# RasPi-feather.net
KiCad netlist of a schematic drawn in EAGLE
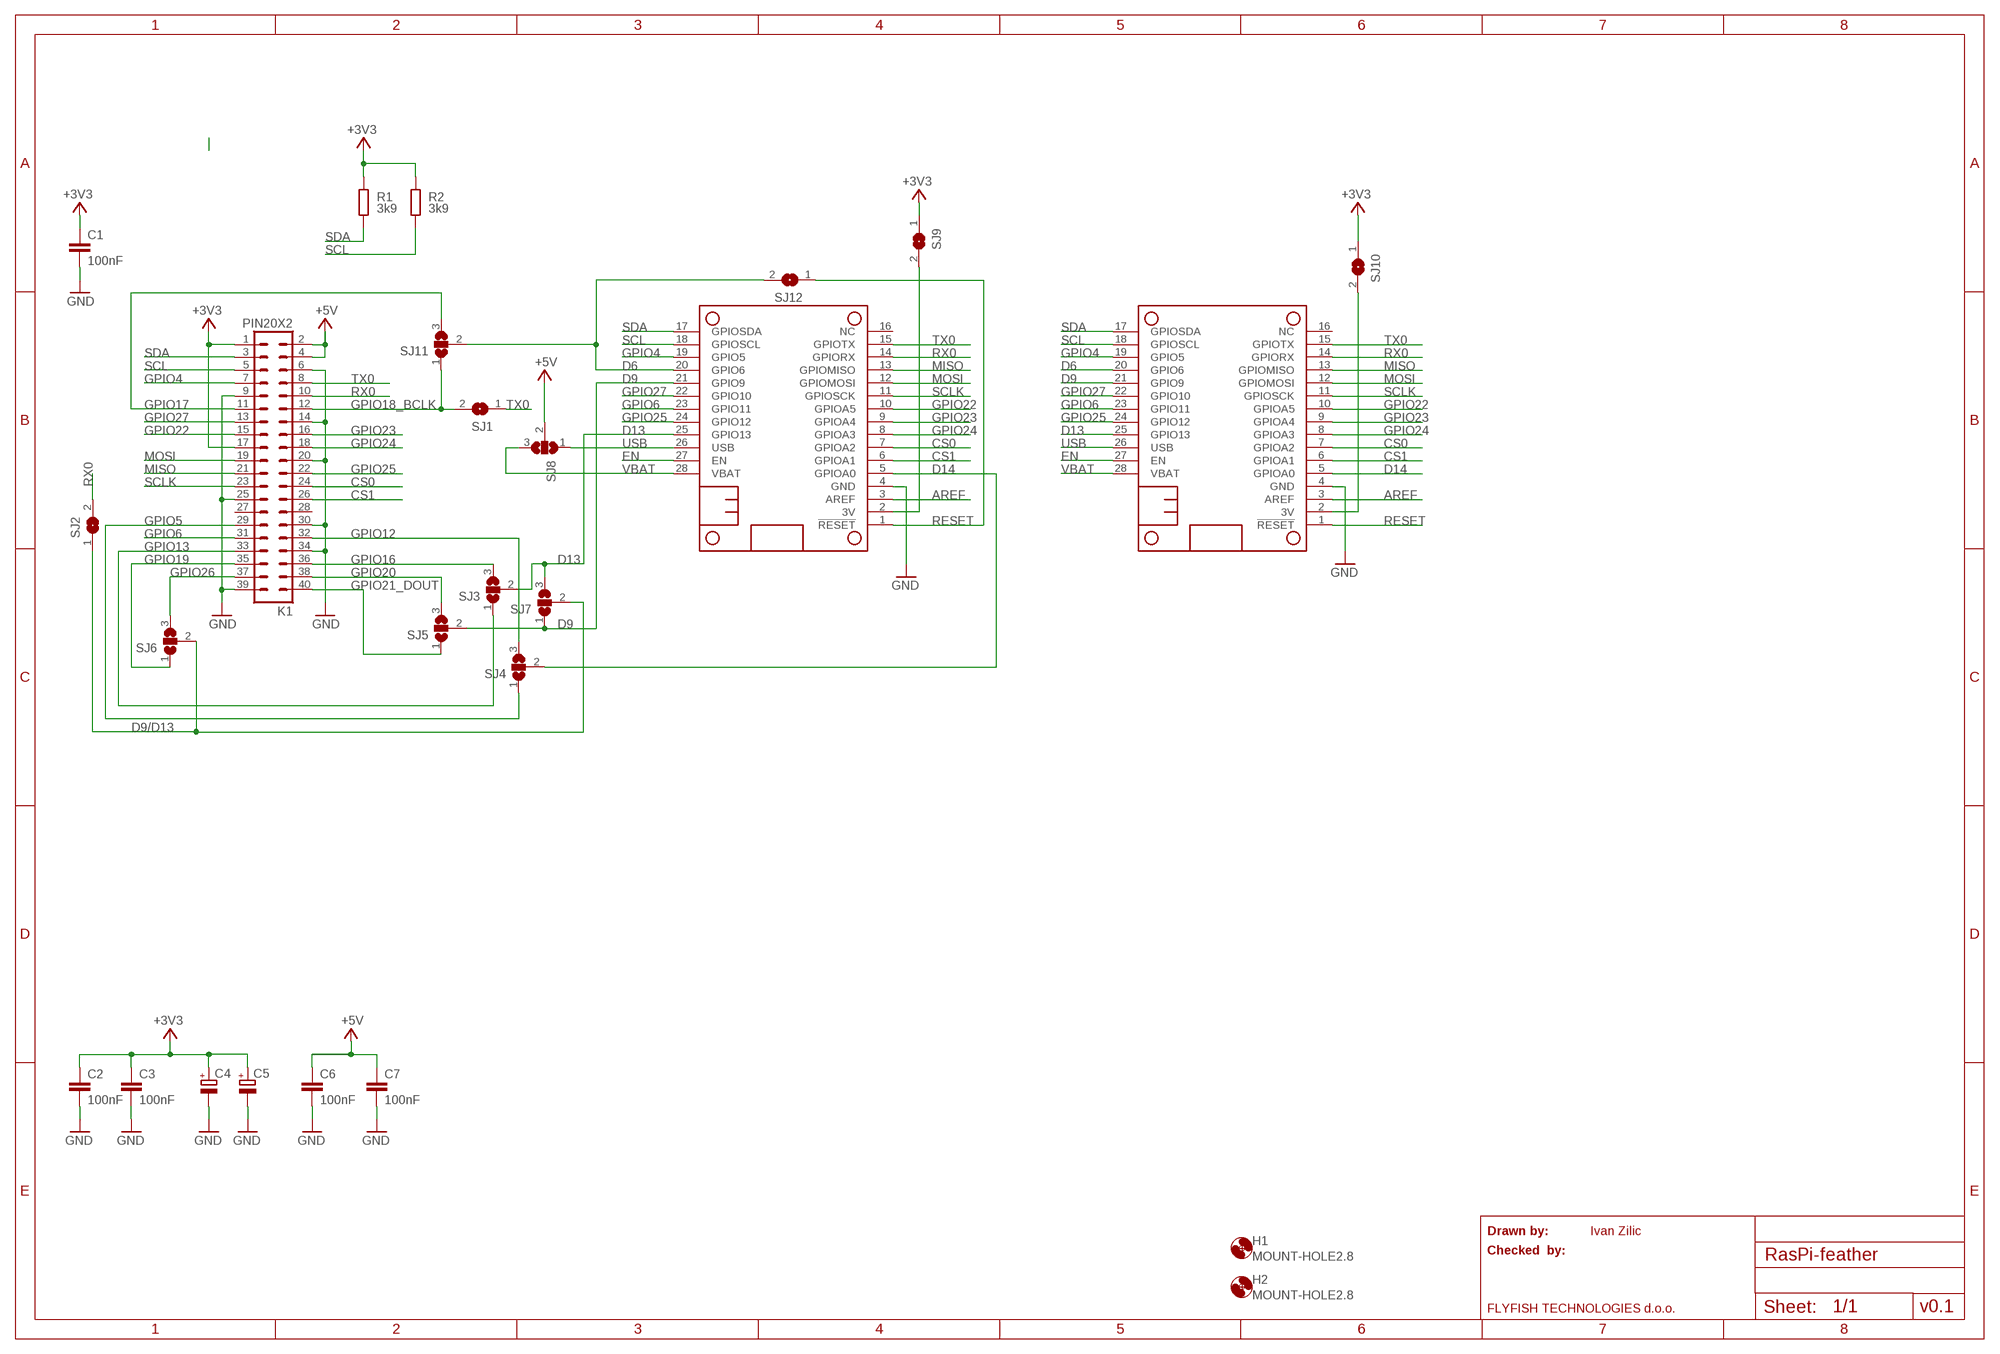
[diagram p0: schematic, sheet 1]

(export (version "E")
  (design (tool "Eeschema 10.0.6"))
  (components
    (comp (ref "C1")
      (value "100nF")
      (footprint "eagle-import:C0805K")
      (libsource (lib "eagle-import") (part "C-EUC0805K"))
    )
    (comp (ref "C2")
      (value "100nF")
      (footprint "eagle-import:C0805K")
      (libsource (lib "eagle-import") (part "C-EUC0805K"))
    )
    (comp (ref "C3")
      (value "100nF")
      (footprint "eagle-import:C0805K")
      (libsource (lib "eagle-import") (part "C-EUC0805K"))
    )
    (comp (ref "C4")
      (value "CPOL-EUSMCD")
      (footprint "eagle-import:SMC_D")
      (libsource (lib "eagle-import") (part "CPOL-EUSMCD"))
    )
    (comp (ref "C5")
      (value "CPOL-EUSMCD")
      (footprint "eagle-import:SMC_D")
      (libsource (lib "eagle-import") (part "CPOL-EUSMCD"))
    )
    (comp (ref "C6")
      (value "100nF")
      (footprint "eagle-import:C0805K")
      (libsource (lib "eagle-import") (part "C-EUC0805K"))
    )
    (comp (ref "C7")
      (value "100nF")
      (footprint "eagle-import:C0805K")
      (libsource (lib "eagle-import") (part "C-EUC0805K"))
    )
    (comp (ref "H1")
      (value "MOUNT-HOLE2.8")
      (footprint "eagle-import:2,8")
      (libsource (lib "eagle-import") (part "MOUNT-HOLE2.8"))
    )
    (comp (ref "H2")
      (value "MOUNT-HOLE2.8")
      (footprint "eagle-import:2,8")
      (libsource (lib "eagle-import") (part "MOUNT-HOLE2.8"))
    )
    (comp (ref "K1")
      (value "PIN20X2")
      (footprint "eagle-import:PIN_20X2")
      (libsource (lib "eagle-import") (part "PIN20X2"))
    )
    (comp (ref "MS1")
      (value "FEATHERWING_NODIM")
      (footprint "eagle-import:FEATHERWING_DIM")
      (libsource (lib "eagle-import") (part "FEATHERWING_NODIM"))
    )
    (comp (ref "MS2")
      (value "FEATHERWING_NODIM")
      (footprint "eagle-import:FEATHERWING_DIM")
      (libsource (lib "eagle-import") (part "FEATHERWING_NODIM"))
    )
    (comp (ref "R1")
      (value "3k9")
      (footprint "eagle-import:M0805")
      (fields (field (name "TOLERANCE") "5%"))
      (libsource (lib "eagle-import") (part "R-EU_M0805"))
    )
    (comp (ref "R2")
      (value "3k9")
      (footprint "eagle-import:M0805")
      (fields (field (name "TOLERANCE") "5%"))
      (libsource (lib "eagle-import") (part "R-EU_M0805"))
    )
    (comp (ref "SJ1") (value "SJ") (footprint "eagle-import:SJ") (libsource (lib "eagle-import") (part "SJ")))
    (comp (ref "SJ2") (value "SJ") (footprint "eagle-import:SJ") (libsource (lib "eagle-import") (part "SJ")))
    (comp (ref "SJ3")
      (value "SJ2W")
      (footprint "eagle-import:SJ_2")
      (libsource (lib "eagle-import") (part "SJ2W"))
    )
    (comp (ref "SJ4")
      (value "SJ2W")
      (footprint "eagle-import:SJ_2")
      (libsource (lib "eagle-import") (part "SJ2W"))
    )
    (comp (ref "SJ5")
      (value "SJ2W")
      (footprint "eagle-import:SJ_2")
      (libsource (lib "eagle-import") (part "SJ2W"))
    )
    (comp (ref "SJ6")
      (value "SJ2W")
      (footprint "eagle-import:SJ_2")
      (libsource (lib "eagle-import") (part "SJ2W"))
    )
    (comp (ref "SJ7")
      (value "SJ2W")
      (footprint "eagle-import:SJ_2")
      (libsource (lib "eagle-import") (part "SJ2W"))
    )
    (comp (ref "SJ8")
      (value "SJ2W")
      (footprint "eagle-import:SJ_2")
      (libsource (lib "eagle-import") (part "SJ2W"))
    )
    (comp (ref "SJ9") (value "SJ") (footprint "eagle-import:SJ") (libsource (lib "eagle-import") (part "SJ")))
    (comp (ref "SJ10")
      (value "SJ")
      (footprint "eagle-import:SJ")
      (libsource (lib "eagle-import") (part "SJ"))
    )
    (comp (ref "SJ11")
      (value "SJ2W")
      (footprint "eagle-import:SJ_2")
      (libsource (lib "eagle-import") (part "SJ2W"))
    )
    (comp (ref "SJ12")
      (value "SJ")
      (footprint "eagle-import:SJ")
      (libsource (lib "eagle-import") (part "SJ"))
    )
  )
  (nets
    (net (code "1") (name "+3V3") (class "Default")
      (node (ref "C1") (pin "1") (pinfunction "1_1") (pintype "passive"))
      (node (ref "C2") (pin "1") (pinfunction "1_1") (pintype "passive"))
      (node (ref "C3") (pin "1") (pinfunction "1_1") (pintype "passive"))
      (node (ref "C4") (pin "+") (pinfunction "+_+") (pintype "passive"))
      (node (ref "C5") (pin "+") (pinfunction "+_+") (pintype "passive"))
      (node (ref "K1") (pin "1") (pinfunction "1_1") (pintype "passive"))
      (node (ref "K1") (pin "17") (pinfunction "17_17") (pintype "passive"))
      (node (ref "R1") (pin "2") (pinfunction "2_2") (pintype "passive"))
      (node (ref "R2") (pin "2") (pinfunction "2_2") (pintype "passive"))
      (node (ref "SJ10") (pin "1") (pinfunction "1_1") (pintype "passive"))
      (node (ref "SJ9") (pin "1") (pinfunction "1_1") (pintype "passive"))
    )
    (net (code "2") (name "+5V") (class "Default")
      (node (ref "C6") (pin "1") (pinfunction "1_1") (pintype "passive"))
      (node (ref "C7") (pin "1") (pinfunction "1_1") (pintype "passive"))
      (node (ref "K1") (pin "2") (pinfunction "2_2") (pintype "passive"))
      (node (ref "K1") (pin "4") (pinfunction "4_4") (pintype "passive"))
      (node (ref "SJ8") (pin "2") (pinfunction "2_2") (pintype "passive"))
    )
    (net (code "3") (name "/AREF") (class "Default")
      (node (ref "MS1") (pin "3") (pinfunction "AREF_3") (pintype "passive"))
      (node (ref "MS2") (pin "3") (pinfunction "AREF_3") (pintype "passive"))
    )
    (net (code "4") (name "/CS0") (class "Default")
      (node (ref "K1") (pin "24") (pinfunction "24_24") (pintype "passive"))
      (node (ref "MS1") (pin "7") (pinfunction "GPIOA2_7") (pintype "bidirectional"))
      (node (ref "MS2") (pin "7") (pinfunction "GPIOA2_7") (pintype "bidirectional"))
    )
    (net (code "5") (name "/CS1") (class "Default")
      (node (ref "K1") (pin "26") (pinfunction "26_26") (pintype "passive"))
      (node (ref "MS1") (pin "6") (pinfunction "GPIOA1_6") (pintype "bidirectional"))
      (node (ref "MS2") (pin "6") (pinfunction "GPIOA1_6") (pintype "bidirectional"))
    )
    (net (code "6") (name "/D6") (class "Default")
      (node (ref "MS1") (pin "20") (pinfunction "GPIO6_20") (pintype "bidirectional"))
      (node (ref "MS2") (pin "20") (pinfunction "GPIO6_20") (pintype "bidirectional"))
      (node (ref "SJ11") (pin "2") (pinfunction "2_2") (pintype "passive"))
      (node (ref "SJ12") (pin "2") (pinfunction "2_2") (pintype "passive"))
    )
    (net (code "7") (name "/D9") (class "Default")
      (node (ref "MS1") (pin "21") (pinfunction "GPIO9_21") (pintype "bidirectional"))
      (node (ref "MS2") (pin "21") (pinfunction "GPIO9_21") (pintype "bidirectional"))
      (node (ref "SJ5") (pin "2") (pinfunction "2_2") (pintype "passive"))
      (node (ref "SJ7") (pin "1") (pinfunction "1_1") (pintype "passive"))
    )
    (net (code "8") (name "/D9{slash}D13") (class "Default")
      (node (ref "SJ2") (pin "1") (pinfunction "1_1") (pintype "passive"))
      (node (ref "SJ6") (pin "2") (pinfunction "2_2") (pintype "passive"))
      (node (ref "SJ7") (pin "2") (pinfunction "2_2") (pintype "passive"))
    )
    (net (code "9") (name "/D13") (class "Default")
      (node (ref "MS1") (pin "25") (pinfunction "GPIO13_25") (pintype "bidirectional"))
      (node (ref "MS2") (pin "25") (pinfunction "GPIO13_25") (pintype "bidirectional"))
      (node (ref "SJ3") (pin "2") (pinfunction "2_2") (pintype "passive"))
      (node (ref "SJ7") (pin "3") (pinfunction "3_3") (pintype "passive"))
    )
    (net (code "10") (name "/D14") (class "Default")
      (node (ref "MS1") (pin "5") (pinfunction "GPIOA0_5") (pintype "bidirectional"))
      (node (ref "MS2") (pin "5") (pinfunction "GPIOA0_5") (pintype "bidirectional"))
      (node (ref "SJ4") (pin "2") (pinfunction "2_2") (pintype "passive"))
    )
    (net (code "11") (name "/EN") (class "Default")
      (node (ref "MS1") (pin "27") (pinfunction "EN_27") (pintype "passive"))
      (node (ref "MS2") (pin "27") (pinfunction "EN_27") (pintype "passive"))
    )
    (net (code "12") (name "/GPIO4") (class "Default")
      (node (ref "K1") (pin "7") (pinfunction "7_7") (pintype "passive"))
      (node (ref "MS1") (pin "19") (pinfunction "GPIO5_19") (pintype "bidirectional"))
      (node (ref "MS2") (pin "19") (pinfunction "GPIO5_19") (pintype "bidirectional"))
    )
    (net (code "13") (name "/GPIO5") (class "Default")
      (node (ref "K1") (pin "29") (pinfunction "29_29") (pintype "passive"))
      (node (ref "SJ4") (pin "1") (pinfunction "1_1") (pintype "passive"))
    )
    (net (code "14") (name "/GPIO6") (class "Default")
      (node (ref "K1") (pin "31") (pinfunction "31_31") (pintype "passive"))
      (node (ref "MS1") (pin "23") (pinfunction "GPIO11_23") (pintype "bidirectional"))
      (node (ref "MS2") (pin "23") (pinfunction "GPIO11_23") (pintype "bidirectional"))
    )
    (net (code "15") (name "/GPIO12") (class "Default")
      (node (ref "K1") (pin "32") (pinfunction "32_32") (pintype "passive"))
      (node (ref "SJ4") (pin "3") (pinfunction "3_3") (pintype "passive"))
    )
    (net (code "16") (name "/GPIO13") (class "Default")
      (node (ref "K1") (pin "33") (pinfunction "33_33") (pintype "passive"))
      (node (ref "SJ3") (pin "1") (pinfunction "1_1") (pintype "passive"))
    )
    (net (code "17") (name "/GPIO16") (class "Default")
      (node (ref "K1") (pin "36") (pinfunction "36_36") (pintype "passive"))
      (node (ref "SJ3") (pin "3") (pinfunction "3_3") (pintype "passive"))
    )
    (net (code "18") (name "/GPIO17") (class "Default")
      (node (ref "K1") (pin "11") (pinfunction "11_11") (pintype "passive"))
      (node (ref "SJ11") (pin "3") (pinfunction "3_3") (pintype "passive"))
    )
    (net (code "19") (name "/GPIO18_BCLK") (class "Default")
      (node (ref "K1") (pin "12") (pinfunction "12_12") (pintype "passive"))
      (node (ref "SJ1") (pin "2") (pinfunction "2_2") (pintype "passive"))
      (node (ref "SJ11") (pin "1") (pinfunction "1_1") (pintype "passive"))
    )
    (net (code "20") (name "/GPIO19") (class "Default")
      (node (ref "K1") (pin "35") (pinfunction "35_35") (pintype "passive"))
      (node (ref "SJ6") (pin "1") (pinfunction "1_1") (pintype "passive"))
    )
    (net (code "21") (name "/GPIO20") (class "Default")
      (node (ref "K1") (pin "38") (pinfunction "38_38") (pintype "passive"))
      (node (ref "SJ5") (pin "3") (pinfunction "3_3") (pintype "passive"))
    )
    (net (code "22") (name "/GPIO21_DOUT") (class "Default")
      (node (ref "K1") (pin "40") (pinfunction "40_40") (pintype "passive"))
      (node (ref "SJ5") (pin "1") (pinfunction "1_1") (pintype "passive"))
    )
    (net (code "23") (name "/GPIO22") (class "Default")
      (node (ref "K1") (pin "15") (pinfunction "15_15") (pintype "passive"))
      (node (ref "MS1") (pin "10") (pinfunction "GPIOA5_10") (pintype "bidirectional"))
      (node (ref "MS2") (pin "10") (pinfunction "GPIOA5_10") (pintype "bidirectional"))
    )
    (net (code "24") (name "/GPIO23") (class "Default")
      (node (ref "K1") (pin "16") (pinfunction "16_16") (pintype "passive"))
      (node (ref "MS1") (pin "9") (pinfunction "GPIOA4_9") (pintype "bidirectional"))
      (node (ref "MS2") (pin "9") (pinfunction "GPIOA4_9") (pintype "bidirectional"))
    )
    (net (code "25") (name "/GPIO24") (class "Default")
      (node (ref "K1") (pin "18") (pinfunction "18_18") (pintype "passive"))
      (node (ref "MS1") (pin "8") (pinfunction "GPIOA3_8") (pintype "bidirectional"))
      (node (ref "MS2") (pin "8") (pinfunction "GPIOA3_8") (pintype "bidirectional"))
    )
    (net (code "26") (name "/GPIO25") (class "Default")
      (node (ref "K1") (pin "22") (pinfunction "22_22") (pintype "passive"))
      (node (ref "MS1") (pin "24") (pinfunction "GPIO12_24") (pintype "bidirectional"))
      (node (ref "MS2") (pin "24") (pinfunction "GPIO12_24") (pintype "bidirectional"))
    )
    (net (code "27") (name "/GPIO26") (class "Default")
      (node (ref "K1") (pin "37") (pinfunction "37_37") (pintype "passive"))
      (node (ref "SJ6") (pin "3") (pinfunction "3_3") (pintype "passive"))
    )
    (net (code "28") (name "/GPIO27") (class "Default")
      (node (ref "K1") (pin "13") (pinfunction "13_13") (pintype "passive"))
      (node (ref "MS1") (pin "22") (pinfunction "GPIO10_22") (pintype "bidirectional"))
      (node (ref "MS2") (pin "22") (pinfunction "GPIO10_22") (pintype "bidirectional"))
    )
    (net (code "29") (name "/MISO") (class "Default")
      (node (ref "K1") (pin "21") (pinfunction "21_21") (pintype "passive"))
      (node (ref "MS1") (pin "13") (pinfunction "GPIOMISO_13") (pintype "bidirectional"))
      (node (ref "MS2") (pin "13") (pinfunction "GPIOMISO_13") (pintype "bidirectional"))
    )
    (net (code "30") (name "/MOSI") (class "Default")
      (node (ref "K1") (pin "19") (pinfunction "19_19") (pintype "passive"))
      (node (ref "MS1") (pin "12") (pinfunction "GPIOMOSI_12") (pintype "bidirectional"))
      (node (ref "MS2") (pin "12") (pinfunction "GPIOMOSI_12") (pintype "bidirectional"))
    )
    (net (code "31") (name "/RESET") (class "Default")
      (node (ref "MS1") (pin "1") (pinfunction "~{RESET}_1") (pintype "input"))
      (node (ref "MS2") (pin "1") (pinfunction "~{RESET}_1") (pintype "input"))
      (node (ref "SJ12") (pin "1") (pinfunction "1_1") (pintype "passive"))
    )
    (net (code "32") (name "/RX0") (class "Default")
      (node (ref "K1") (pin "10") (pinfunction "10_10") (pintype "passive"))
      (node (ref "MS1") (pin "14") (pinfunction "GPIORX_14") (pintype "bidirectional"))
      (node (ref "MS2") (pin "14") (pinfunction "GPIORX_14") (pintype "bidirectional"))
      (node (ref "SJ2") (pin "2") (pinfunction "2_2") (pintype "passive"))
    )
    (net (code "33") (name "/SCL") (class "Default")
      (node (ref "K1") (pin "5") (pinfunction "5_5") (pintype "passive"))
      (node (ref "MS1") (pin "18") (pinfunction "GPIOSCL_18") (pintype "bidirectional"))
      (node (ref "MS2") (pin "18") (pinfunction "GPIOSCL_18") (pintype "bidirectional"))
      (node (ref "R2") (pin "1") (pinfunction "1_1") (pintype "passive"))
    )
    (net (code "34") (name "/SCLK") (class "Default")
      (node (ref "K1") (pin "23") (pinfunction "23_23") (pintype "passive"))
      (node (ref "MS1") (pin "11") (pinfunction "GPIOSCK_11") (pintype "bidirectional"))
      (node (ref "MS2") (pin "11") (pinfunction "GPIOSCK_11") (pintype "bidirectional"))
    )
    (net (code "35") (name "/SDA") (class "Default")
      (node (ref "K1") (pin "3") (pinfunction "3_3") (pintype "passive"))
      (node (ref "MS1") (pin "17") (pinfunction "GPIOSDA_17") (pintype "bidirectional"))
      (node (ref "MS2") (pin "17") (pinfunction "GPIOSDA_17") (pintype "bidirectional"))
      (node (ref "R1") (pin "1") (pinfunction "1_1") (pintype "passive"))
    )
    (net (code "36") (name "/TX0") (class "Default")
      (node (ref "K1") (pin "8") (pinfunction "8_8") (pintype "passive"))
      (node (ref "MS1") (pin "15") (pinfunction "GPIOTX_15") (pintype "bidirectional"))
      (node (ref "MS2") (pin "15") (pinfunction "GPIOTX_15") (pintype "bidirectional"))
      (node (ref "SJ1") (pin "1") (pinfunction "1_1") (pintype "passive"))
    )
    (net (code "37") (name "/USB") (class "Default")
      (node (ref "MS1") (pin "26") (pinfunction "USB_26") (pintype "power_in"))
      (node (ref "MS2") (pin "26") (pinfunction "USB_26") (pintype "power_in"))
      (node (ref "SJ8") (pin "1") (pinfunction "1_1") (pintype "passive"))
    )
    (net (code "38") (name "/VBAT") (class "Default")
      (node (ref "MS1") (pin "28") (pinfunction "VBAT_28") (pintype "power_in"))
      (node (ref "MS2") (pin "28") (pinfunction "VBAT_28") (pintype "power_in"))
      (node (ref "SJ8") (pin "3") (pinfunction "3_3") (pintype "passive"))
    )
    (net (code "39") (name "GND") (class "Default")
      (node (ref "C1") (pin "2") (pinfunction "2_2") (pintype "passive"))
      (node (ref "C2") (pin "2") (pinfunction "2_2") (pintype "passive"))
      (node (ref "C3") (pin "2") (pinfunction "2_2") (pintype "passive"))
      (node (ref "C4") (pin "-") (pinfunction "-_-") (pintype "passive"))
      (node (ref "C5") (pin "-") (pinfunction "-_-") (pintype "passive"))
      (node (ref "C6") (pin "2") (pinfunction "2_2") (pintype "passive"))
      (node (ref "C7") (pin "2") (pinfunction "2_2") (pintype "passive"))
      (node (ref "K1") (pin "14") (pinfunction "14_14") (pintype "passive"))
      (node (ref "K1") (pin "20") (pinfunction "20_20") (pintype "passive"))
      (node (ref "K1") (pin "25") (pinfunction "25_25") (pintype "passive"))
      (node (ref "K1") (pin "30") (pinfunction "30_30") (pintype "passive"))
      (node (ref "K1") (pin "34") (pinfunction "34_34") (pintype "passive"))
      (node (ref "K1") (pin "39") (pinfunction "39_39") (pintype "passive"))
      (node (ref "K1") (pin "6") (pinfunction "6_6") (pintype "passive"))
      (node (ref "K1") (pin "9") (pinfunction "9_9") (pintype "passive"))
      (node (ref "MS1") (pin "4") (pinfunction "GND_4") (pintype "power_in"))
      (node (ref "MS2") (pin "4") (pinfunction "GND_4") (pintype "power_in"))
    )
    (net (code "40") (name "Net-(MS1-3V)") (class "Default")
      (node (ref "MS1") (pin "2") (pinfunction "3V_2") (pintype "power_in"))
      (node (ref "SJ9") (pin "2") (pinfunction "2_2") (pintype "passive"))
    )
    (net (code "41") (name "Net-(MS2-3V)") (class "Default")
      (node (ref "MS2") (pin "2") (pinfunction "3V_2") (pintype "power_in"))
      (node (ref "SJ10") (pin "2") (pinfunction "2_2") (pintype "passive"))
    )
    (net (code "42") (name "unconnected-(K1-Pad27)") (class "Default")
      (node (ref "K1") (pin "27") (pinfunction "27_27") (pintype "passive"))
    )
    (net (code "43") (name "unconnected-(K1-Pad28)") (class "Default")
      (node (ref "K1") (pin "28") (pinfunction "28_28") (pintype "passive"))
    )
    (net (code "44") (name "unconnected-(MS1-NC-Pad16)") (class "Default")
      (node (ref "MS1") (pin "16") (pinfunction "NC_16") (pintype "passive"))
    )
    (net (code "45") (name "unconnected-(MS2-NC-Pad16)") (class "Default")
      (node (ref "MS2") (pin "16") (pinfunction "NC_16") (pintype "passive"))
    )
  )
)
